# Sheet3.net
KiCad netlist of a schematic drawn in Altium Designer
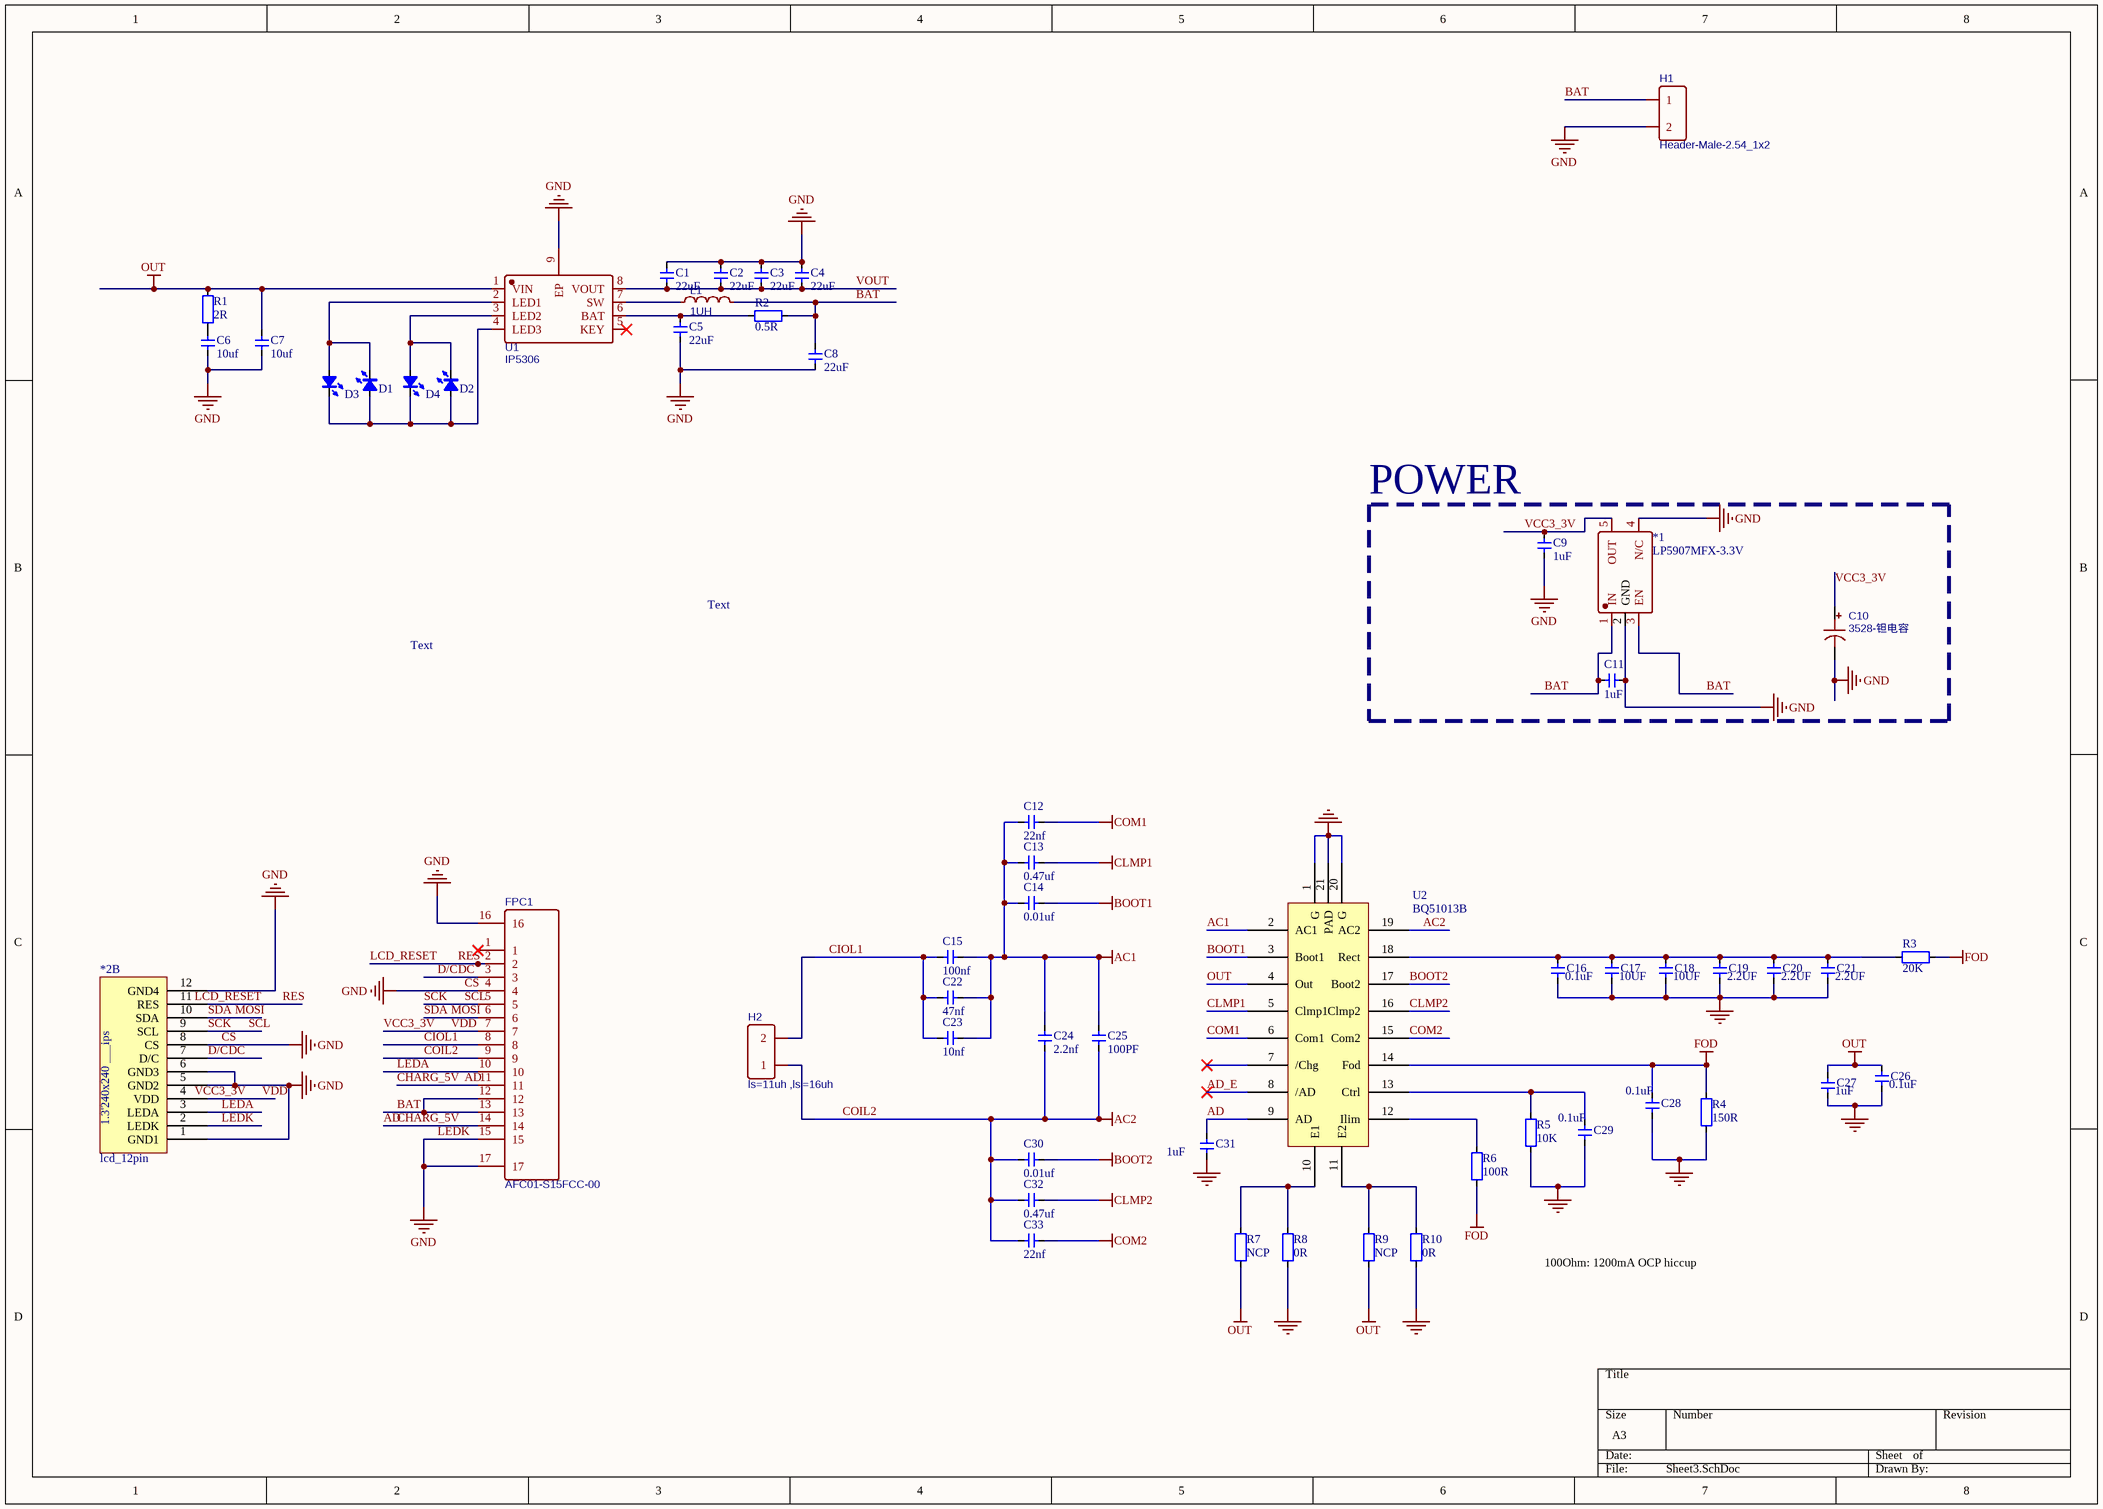
[diagram p0: Sheet3.SchDoc]

(export (version "E")
  (design (tool "Eeschema 10.0.6"))
  (components
    (comp (ref "*1")
      (value "LP5907MFX-3.3V")
      (footprint "LP5907MFX-3.3V")
      (libsource (lib "MCU") (part "LP5907MFX-3.3V"))
    )
    (comp (ref "*2")
      (value "lcd_12pin")
      (footprint "1.3‘240x240__ips")
      (libsource (lib "接插件") (part "lcd_12pin"))
    )
    (comp (ref "C1")
      (value "22uF")
      (footprint "CAP_0402")
      (description "Capacitor")
      (libsource (lib "BASE") (part "电容-0402"))
    )
    (comp (ref "C2")
      (value "22uF")
      (footprint "CAP_0402")
      (description "Capacitor")
      (libsource (lib "BASE") (part "电容-0402"))
    )
    (comp (ref "C3")
      (value "22uF")
      (footprint "CAP_0402")
      (description "Capacitor")
      (libsource (lib "BASE") (part "电容-0402"))
    )
    (comp (ref "C4")
      (value "22uF")
      (footprint "CAP_0402")
      (description "Capacitor")
      (libsource (lib "BASE") (part "电容-0402"))
    )
    (comp (ref "C5")
      (value "22uF")
      (footprint "CAP_0402")
      (description "Capacitor")
      (libsource (lib "BASE") (part "电容-0402"))
    )
    (comp (ref "C6")
      (value "10uf")
      (footprint "CAP_0402")
      (description "Capacitor")
      (libsource (lib "BASE") (part "电容-0402"))
    )
    (comp (ref "C7")
      (value "10uf")
      (footprint "CAP_0402")
      (description "Capacitor")
      (libsource (lib "BASE") (part "电容-0402"))
    )
    (comp (ref "C8")
      (value "22uF")
      (footprint "CAP_0402")
      (description "Capacitor")
      (libsource (lib "BASE") (part "电容-0402"))
    )
    (comp (ref "C9")
      (value "1uF")
      (footprint "CAP_0402")
      (description "Capacitor")
      (libsource (lib "BASE") (part "电容-0402"))
    )
    (comp (ref "C10")
      (value "3528-钽电容")
      (footprint "CAP-SMD_L3.5-W2.8")
      (fields
        (field (name "BOM_SUPPLIER PART") "C435294")
        (field (name "BOM_MANUFACTURER PART") "CA45-B016M476T")
        (field (name "CONTRIBUTOR") "LCSC")
      )
      (libsource (lib "BASE") (part "3528-钽电容"))
    )
    (comp (ref "C11")
      (value "1uF")
      (footprint "CAP_0402")
      (description "Capacitor")
      (libsource (lib "BASE") (part "电容-0402"))
    )
    (comp (ref "C12")
      (value "22nf")
      (footprint "CAP_0402")
      (description "Capacitor")
      (libsource (lib "BASE") (part "电容-0402"))
    )
    (comp (ref "C13")
      (value "0.47uf")
      (footprint "CAP_0402")
      (description "Capacitor")
      (libsource (lib "BASE") (part "电容-0402"))
    )
    (comp (ref "C14")
      (value "0.01uf")
      (footprint "CAP_0402")
      (description "Capacitor")
      (libsource (lib "BASE") (part "电容-0402"))
    )
    (comp (ref "C15")
      (value "100nf")
      (footprint "CAP_0402")
      (description "Capacitor")
      (libsource (lib "BASE") (part "电容-0402"))
    )
    (comp (ref "C16")
      (value "0.1uF")
      (footprint "CAP_0402")
      (description "Capacitor")
      (libsource (lib "BASE") (part "电容-0402"))
    )
    (comp (ref "C17")
      (value "10UF")
      (footprint "CAP_0402")
      (description "Capacitor")
      (libsource (lib "BASE") (part "电容-0402"))
    )
    (comp (ref "C18")
      (value "10UF")
      (footprint "CAP_0402")
      (description "Capacitor")
      (libsource (lib "BASE") (part "电容-0402"))
    )
    (comp (ref "C19")
      (value "2.2UF")
      (footprint "CAP_0402")
      (description "Capacitor")
      (libsource (lib "BASE") (part "电容-0402"))
    )
    (comp (ref "C20")
      (value "2.2UF")
      (footprint "CAP_0402")
      (description "Capacitor")
      (libsource (lib "BASE") (part "电容-0402"))
    )
    (comp (ref "C21")
      (value "2.2UF")
      (footprint "CAP_0402")
      (description "Capacitor")
      (libsource (lib "BASE") (part "电容-0402"))
    )
    (comp (ref "C22")
      (value "47nf")
      (footprint "CAP_0402")
      (description "Capacitor")
      (libsource (lib "BASE") (part "电容-0402"))
    )
    (comp (ref "C23")
      (value "10nf")
      (footprint "CAP_0402")
      (description "Capacitor")
      (libsource (lib "BASE") (part "电容-0402"))
    )
    (comp (ref "C24")
      (value "2.2nf")
      (footprint "CAP_0402")
      (description "Capacitor")
      (libsource (lib "BASE") (part "电容-0402"))
    )
    (comp (ref "C25")
      (value "100PF")
      (footprint "CAP_0402")
      (description "Capacitor")
      (libsource (lib "BASE") (part "电容-0402"))
    )
    (comp (ref "C26")
      (value "0.1uF")
      (footprint "CAP_0402")
      (description "Capacitor")
      (libsource (lib "BASE") (part "电容-0402"))
    )
    (comp (ref "C27")
      (value "1uF")
      (footprint "CAP_0402")
      (description "Capacitor")
      (libsource (lib "BASE") (part "电容-0402"))
    )
    (comp (ref "C28")
      (value "0.1uF")
      (footprint "CAP_0402")
      (description "Capacitor")
      (libsource (lib "BASE") (part "电容-0402"))
    )
    (comp (ref "C29")
      (value "0.1uF")
      (footprint "CAP_0402")
      (description "Capacitor")
      (libsource (lib "BASE") (part "电容-0402"))
    )
    (comp (ref "C30")
      (value "0.01uf")
      (footprint "CAP_0402")
      (description "Capacitor")
      (libsource (lib "BASE") (part "电容-0402"))
    )
    (comp (ref "C31")
      (value "1uF")
      (footprint "CAP_0402")
      (description "Capacitor")
      (libsource (lib "BASE") (part "电容-0402"))
    )
    (comp (ref "C32")
      (value "0.47uf")
      (footprint "CAP_0402")
      (description "Capacitor")
      (libsource (lib "BASE") (part "电容-0402"))
    )
    (comp (ref "C33")
      (value "22nf")
      (footprint "CAP_0402")
      (description "Capacitor")
      (libsource (lib "BASE") (part "电容-0402"))
    )
    (comp (ref "D1")
      (value "color?")
      (footprint "LED_0402_GREEN")
      (description "LED")
      (libsource (lib "BASE") (part "LED灯_0402"))
    )
    (comp (ref "D2")
      (value "color?")
      (footprint "LED_0402_GREEN")
      (description "LED")
      (libsource (lib "BASE") (part "LED灯_0402"))
    )
    (comp (ref "D3")
      (value "color?")
      (footprint "LED_0402_GREEN")
      (description "LED")
      (libsource (lib "") (part "LED灯_0402_1"))
    )
    (comp (ref "D4")
      (value "color?")
      (footprint "LED_0402_GREEN")
      (description "LED")
      (libsource (lib "") (part "LED灯_0402_1"))
    )
    (comp (ref "FPC1")
      (value "AFC01-S15FCC-00")
      (footprint "FPC-SMD_AFC01-S15FCC-00")
      (fields (field (name "BOM_SUPPLIER PART") "C262271") (field (name "CONTRIBUTOR") "LCSC"))
      (libsource (lib "接插件") (part "FPC-15P-0.5-AFC01-S15FCC-00"))
    )
    (comp (ref "H1")
      (value "Header-Male-2.54_1x2")
      (footprint "HDR-TH_2P-P2.54-V")
      (fields (field (name "BOM_MANUFACTURER PART") "826629-2") (field (name "BOM_SUPPLIER PART") "C86471"))
      (libsource (lib "接插件") (part "排针-1*2"))
    )
    (comp (ref "H2")
      (value "ls=11uh ,ls'=16uh")
      (footprint "HDR-TH_2P-P2.54-V")
      (fields (field (name "BOM_MANUFACTURER PART") "826629-2") (field (name "BOM_SUPPLIER PART") "C86471"))
      (libsource (lib "接插件") (part "排针-1*2"))
    )
    (comp (ref "L1")
      (value "1UH")
      (footprint "IND-SMD_L4.2-W4.2_MS0420-XX")
      (description "电感-0420")
      (fields
        (field (name "BOM_SUPPLIER PART") "C380158")
        (field (name "BOM_MANUFACTURER PART") "MS0420-100M")
        (field (name "CONTRIBUTOR") "LCSC")
      )
      (libsource (lib "BASE") (part "电感-0420"))
    )
    (comp (ref "R1")
      (value "2R")
      (footprint "RES_0402")
      (description "Resistor")
      (libsource (lib "") (part "电阻-0402_1"))
    )
    (comp (ref "R2")
      (value "0.5R")
      (footprint "R0603")
      (description "Resistor")
      (libsource (lib "BASE") (part "电阻-0603"))
    )
    (comp (ref "R3")
      (value "20K")
      (footprint "RES_0402")
      (description "Resistor")
      (libsource (lib "BASE") (part "电阻-0402"))
    )
    (comp (ref "R4")
      (value "150R")
      (footprint "RES_0402")
      (description "Resistor")
      (libsource (lib "") (part "电阻-0402_1"))
    )
    (comp (ref "R5")
      (value "10K")
      (footprint "RES_0402")
      (description "Resistor")
      (libsource (lib "") (part "电阻-0402_1"))
    )
    (comp (ref "R6")
      (value "100R")
      (footprint "RES_0402")
      (description "Resistor")
      (libsource (lib "") (part "电阻-0402_1"))
    )
    (comp (ref "R7")
      (value "NCP")
      (footprint "RES_0402")
      (description "Resistor")
      (libsource (lib "") (part "电阻-0402_1"))
    )
    (comp (ref "R8")
      (value "0R")
      (footprint "RES_0402")
      (description "Resistor")
      (libsource (lib "") (part "电阻-0402_1"))
    )
    (comp (ref "R9")
      (value "NCP")
      (footprint "RES_0402")
      (description "Resistor")
      (libsource (lib "") (part "电阻-0402_1"))
    )
    (comp (ref "R10")
      (value "0R")
      (footprint "RES_0402")
      (description "Resistor")
      (libsource (lib "") (part "电阻-0402_1"))
    )
    (comp (ref "U1")
      (value "IP5306")
      (footprint "ESOP-8_L4.9-W3.9-P1.27-LS6.0-BL-EP")
      (description "充电宝芯片_支持边充边放")
      (fields (field (name "BOM_SUPPLIER PART") "C181692") (field (name "CONTRIBUTOR") "LCSC"))
      (libsource (lib "MCU") (part "IP5306"))
    )
    (comp (ref "U2")
      (value "BQ51013B")
      (footprint "IC_MSP430FR2522IRHLR")
      (description "无线充电接受，qi")
      (libsource (lib "Schlib3") (part "BQ51013B"))
    )
  )
  (nets
    (net (code "1") (name "/AD") (class "Default")
      (node (ref "C31") (pin "1") (pinfunction "1_1") (pintype "passive"))
      (node (ref "FPC1") (pin "11") (pinfunction "11_11") (pintype "passive"))
      (node (ref "FPC1") (pin "14") (pinfunction "14_14") (pintype "passive"))
      (node (ref "U2") (pin "9") (pinfunction "AD_9") (pintype "passive"))
    )
    (net (code "2") (name "/AD_E") (class "Default")
      (node (ref "U2") (pin "8") (pinfunction "/AD_8") (pintype "passive+no_connect"))
    )
    (net (code "3") (name "/BAT") (class "Default")
      (node (ref "*1") (pin "1") (pinfunction "IN_1") (pintype "passive"))
      (node (ref "*1") (pin "3") (pinfunction "EN_3") (pintype "passive"))
      (node (ref "C11") (pin "2") (pinfunction "2_2") (pintype "passive"))
      (node (ref "C8") (pin "1") (pinfunction "1_1") (pintype "passive"))
      (node (ref "FPC1") (pin "12") (pinfunction "12_12") (pintype "passive"))
      (node (ref "FPC1") (pin "13") (pinfunction "13_13") (pintype "passive"))
      (node (ref "H1") (pin "1") (pinfunction "1_1") (pintype "passive"))
      (node (ref "L1") (pin "2") (pinfunction "2_2") (pintype "passive"))
      (node (ref "R2") (pin "1") (pinfunction "1_1") (pintype "passive"))
    )
    (net (code "4") (name "/CIOL1") (class "Default")
      (node (ref "C15") (pin "1") (pinfunction "1_1") (pintype "passive"))
      (node (ref "C22") (pin "1") (pinfunction "1_1") (pintype "passive"))
      (node (ref "C23") (pin "1") (pinfunction "1_1") (pintype "passive"))
      (node (ref "FPC1") (pin "8") (pinfunction "8_8") (pintype "passive"))
      (node (ref "H2") (pin "2") (pinfunction "2_2") (pintype "passive"))
    )
    (net (code "5") (name "/DC") (class "Default")
      (node (ref "*2") (pin "7") (pinfunction "D/C_7") (pintype "passive"))
      (node (ref "FPC1") (pin "3") (pinfunction "3_3") (pintype "passive"))
    )
    (net (code "6") (name "/LCD_RESET") (class "Default")
      (node (ref "*2") (pin "11") (pinfunction "RES_11") (pintype "passive"))
      (node (ref "FPC1") (pin "2") (pinfunction "2_2") (pintype "passive"))
    )
    (net (code "7") (name "/LEDA") (class "Default")
      (node (ref "*2") (pin "3") (pinfunction "LEDA_3") (pintype "passive"))
      (node (ref "FPC1") (pin "10") (pinfunction "10_10") (pintype "passive"))
    )
    (net (code "8") (name "/MOSI") (class "Default")
      (node (ref "*2") (pin "10") (pinfunction "SDA_10") (pintype "passive"))
      (node (ref "FPC1") (pin "6") (pinfunction "6_6") (pintype "passive"))
    )
    (net (code "9") (name "/SCK") (class "Default")
      (node (ref "*2") (pin "9") (pinfunction "SCL_9") (pintype "passive"))
      (node (ref "FPC1") (pin "5") (pinfunction "5_5") (pintype "passive"))
    )
    (net (code "10") (name "/VCC3_3V") (class "Default")
      (node (ref "*1") (pin "5") (pinfunction "OUT_5") (pintype "passive"))
      (node (ref "*2") (pin "4") (pinfunction "VDD_4") (pintype "passive"))
      (node (ref "C10") (pin "1") (pinfunction "1_1") (pintype "passive"))
      (node (ref "C9") (pin "1") (pinfunction "1_1") (pintype "passive"))
      (node (ref "FPC1") (pin "7") (pinfunction "7_7") (pintype "passive"))
    )
    (net (code "11") (name "/VOUT") (class "Default")
      (node (ref "C1") (pin "2") (pinfunction "2_2") (pintype "passive"))
      (node (ref "C2") (pin "2") (pinfunction "2_2") (pintype "passive"))
      (node (ref "C3") (pin "2") (pinfunction "2_2") (pintype "passive"))
      (node (ref "C4") (pin "2") (pinfunction "2_2") (pintype "passive"))
      (node (ref "U1") (pin "8") (pinfunction "VOUT_8") (pintype "passive"))
    )
    (net (code "12") (name "AC1") (class "Default")
      (node (ref "C12") (pin "1") (pinfunction "1_1") (pintype "passive"))
      (node (ref "C13") (pin "1") (pinfunction "1_1") (pintype "passive"))
      (node (ref "C14") (pin "1") (pinfunction "1_1") (pintype "passive"))
      (node (ref "C15") (pin "2") (pinfunction "2_2") (pintype "passive"))
      (node (ref "C22") (pin "2") (pinfunction "2_2") (pintype "passive"))
      (node (ref "C23") (pin "2") (pinfunction "2_2") (pintype "passive"))
      (node (ref "C24") (pin "2") (pinfunction "2_2") (pintype "passive"))
      (node (ref "C25") (pin "2") (pinfunction "2_2") (pintype "passive"))
      (node (ref "U2") (pin "2") (pinfunction "AC1_2") (pintype "passive"))
    )
    (net (code "13") (name "AC2") (class "Default")
      (node (ref "C24") (pin "1") (pinfunction "1_1") (pintype "passive"))
      (node (ref "C25") (pin "1") (pinfunction "1_1") (pintype "passive"))
      (node (ref "C30") (pin "1") (pinfunction "1_1") (pintype "passive"))
      (node (ref "C32") (pin "1") (pinfunction "1_1") (pintype "passive"))
      (node (ref "C33") (pin "1") (pinfunction "1_1") (pintype "passive"))
      (node (ref "FPC1") (pin "9") (pinfunction "9_9") (pintype "passive"))
      (node (ref "H2") (pin "1") (pinfunction "1_1") (pintype "passive"))
      (node (ref "U2") (pin "19") (pinfunction "AC2_19") (pintype "passive"))
    )
    (net (code "14") (name "BOOT1") (class "Default")
      (node (ref "C14") (pin "2") (pinfunction "2_2") (pintype "passive"))
      (node (ref "U2") (pin "3") (pinfunction "Boot1_3") (pintype "passive"))
    )
    (net (code "15") (name "BOOT2") (class "Default")
      (node (ref "C30") (pin "2") (pinfunction "2_2") (pintype "passive"))
      (node (ref "U2") (pin "17") (pinfunction "Boot2_17") (pintype "passive"))
    )
    (net (code "16") (name "CLMP1") (class "Default")
      (node (ref "C13") (pin "2") (pinfunction "2_2") (pintype "passive"))
      (node (ref "U2") (pin "5") (pinfunction "Clmp1_5") (pintype "passive"))
    )
    (net (code "17") (name "CLMP2") (class "Default")
      (node (ref "C32") (pin "2") (pinfunction "2_2") (pintype "passive"))
      (node (ref "U2") (pin "16") (pinfunction "Clmp2_16") (pintype "passive"))
    )
    (net (code "18") (name "COM1") (class "Default")
      (node (ref "C12") (pin "2") (pinfunction "2_2") (pintype "passive"))
      (node (ref "U2") (pin "6") (pinfunction "Com1_6") (pintype "passive"))
    )
    (net (code "19") (name "COM2") (class "Default")
      (node (ref "C33") (pin "2") (pinfunction "2_2") (pintype "passive"))
      (node (ref "U2") (pin "15") (pinfunction "Com2_15") (pintype "passive"))
    )
    (net (code "20") (name "FOD") (class "Default")
      (node (ref "C28") (pin "1") (pinfunction "1_1") (pintype "passive"))
      (node (ref "R3") (pin "2") (pinfunction "2_2") (pintype "passive"))
      (node (ref "R4") (pin "1") (pinfunction "1_1") (pintype "passive"))
      (node (ref "R6") (pin "2") (pinfunction "2_2") (pintype "passive"))
      (node (ref "U2") (pin "14") (pinfunction "Fod_14") (pintype "passive"))
    )
    (net (code "21") (name "GND") (class "Default")
      (node (ref "*1") (pin "2") (pinfunction "GND_2") (pintype "passive"))
      (node (ref "*1") (pin "4") (pinfunction "N/C_4") (pintype "passive"))
      (node (ref "*2") (pin "1") (pinfunction "GND1_1") (pintype "passive"))
      (node (ref "*2") (pin "12") (pinfunction "GND4_12") (pintype "passive"))
      (node (ref "*2") (pin "2") (pinfunction "LEDK_2") (pintype "passive"))
      (node (ref "*2") (pin "5") (pinfunction "GND2_5") (pintype "passive"))
      (node (ref "*2") (pin "6") (pinfunction "GND3_6") (pintype "passive"))
      (node (ref "*2") (pin "8") (pinfunction "CS_8") (pintype "passive"))
      (node (ref "C1") (pin "1") (pinfunction "1_1") (pintype "passive"))
      (node (ref "C10") (pin "2") (pinfunction "2_2") (pintype "passive"))
      (node (ref "C11") (pin "1") (pinfunction "1_1") (pintype "passive"))
      (node (ref "C16") (pin "2") (pinfunction "2_2") (pintype "passive"))
      (node (ref "C17") (pin "2") (pinfunction "2_2") (pintype "passive"))
      (node (ref "C18") (pin "2") (pinfunction "2_2") (pintype "passive"))
      (node (ref "C19") (pin "2") (pinfunction "2_2") (pintype "passive"))
      (node (ref "C2") (pin "1") (pinfunction "1_1") (pintype "passive"))
      (node (ref "C20") (pin "2") (pinfunction "2_2") (pintype "passive"))
      (node (ref "C21") (pin "2") (pinfunction "2_2") (pintype "passive"))
      (node (ref "C26") (pin "2") (pinfunction "2_2") (pintype "passive"))
      (node (ref "C27") (pin "2") (pinfunction "2_2") (pintype "passive"))
      (node (ref "C28") (pin "2") (pinfunction "2_2") (pintype "passive"))
      (node (ref "C29") (pin "2") (pinfunction "2_2") (pintype "passive"))
      (node (ref "C3") (pin "1") (pinfunction "1_1") (pintype "passive"))
      (node (ref "C31") (pin "2") (pinfunction "2_2") (pintype "passive"))
      (node (ref "C4") (pin "1") (pinfunction "1_1") (pintype "passive"))
      (node (ref "C5") (pin "2") (pinfunction "2_2") (pintype "passive"))
      (node (ref "C6") (pin "1") (pinfunction "1_1") (pintype "passive"))
      (node (ref "C7") (pin "1") (pinfunction "1_1") (pintype "passive"))
      (node (ref "C8") (pin "2") (pinfunction "2_2") (pintype "passive"))
      (node (ref "C9") (pin "2") (pinfunction "2_2") (pintype "passive"))
      (node (ref "FPC1") (pin "15") (pinfunction "15_15") (pintype "passive"))
      (node (ref "FPC1") (pin "16") (pinfunction "16_16") (pintype "passive"))
      (node (ref "FPC1") (pin "17") (pinfunction "17_17") (pintype "passive"))
      (node (ref "FPC1") (pin "4") (pinfunction "4_4") (pintype "passive"))
      (node (ref "H1") (pin "2") (pinfunction "2_2") (pintype "passive"))
      (node (ref "R10") (pin "2") (pinfunction "2_2") (pintype "passive"))
      (node (ref "R4") (pin "2") (pinfunction "2_2") (pintype "passive"))
      (node (ref "R5") (pin "2") (pinfunction "2_2") (pintype "passive"))
      (node (ref "R8") (pin "2") (pinfunction "2_2") (pintype "passive"))
      (node (ref "U1") (pin "9") (pinfunction "EP_9") (pintype "passive"))
      (node (ref "U2") (pin "1") (pinfunction "G_1") (pintype "passive"))
      (node (ref "U2") (pin "20") (pinfunction "G_20") (pintype "passive"))
      (node (ref "U2") (pin "21") (pinfunction "PAD_21") (pintype "passive"))
    )
    (net (code "22") (name "Net-(C6-Pad2)") (class "Default")
      (node (ref "C6") (pin "2") (pinfunction "2_2") (pintype "passive"))
      (node (ref "R1") (pin "2") (pinfunction "2_2") (pintype "passive"))
    )
    (net (code "23") (name "Net-(D1-A)") (class "Default")
      (node (ref "D1") (pin "1") (pinfunction "A_1") (pintype "passive"))
      (node (ref "D2") (pin "1") (pinfunction "A_1") (pintype "passive"))
      (node (ref "D3") (pin "2") (pinfunction "K_2") (pintype "passive"))
      (node (ref "D4") (pin "2") (pinfunction "K_2") (pintype "passive"))
      (node (ref "U1") (pin "4") (pinfunction "LED3_4") (pintype "passive"))
    )
    (net (code "24") (name "Net-(D1-K)") (class "Default")
      (node (ref "D1") (pin "2") (pinfunction "K_2") (pintype "passive"))
      (node (ref "D3") (pin "1") (pinfunction "A_1") (pintype "passive"))
      (node (ref "U1") (pin "2") (pinfunction "LED1_2") (pintype "passive"))
    )
    (net (code "25") (name "Net-(D2-K)") (class "Default")
      (node (ref "D2") (pin "2") (pinfunction "K_2") (pintype "passive"))
      (node (ref "D4") (pin "1") (pinfunction "A_1") (pintype "passive"))
      (node (ref "U1") (pin "3") (pinfunction "LED2_3") (pintype "passive"))
    )
    (net (code "26") (name "Net-(U1-BAT)") (class "Default")
      (node (ref "C5") (pin "1") (pinfunction "1_1") (pintype "passive"))
      (node (ref "R2") (pin "2") (pinfunction "2_2") (pintype "passive"))
      (node (ref "U1") (pin "6") (pinfunction "BAT_6") (pintype "passive"))
    )
    (net (code "27") (name "Net-(U1-SW)") (class "Default")
      (node (ref "L1") (pin "1") (pinfunction "1_1") (pintype "passive"))
      (node (ref "U1") (pin "7") (pinfunction "SW_7") (pintype "passive"))
    )
    (net (code "28") (name "Net-(U2-Ctrl)") (class "Default")
      (node (ref "C29") (pin "1") (pinfunction "1_1") (pintype "passive"))
      (node (ref "R5") (pin "1") (pinfunction "1_1") (pintype "passive"))
      (node (ref "U2") (pin "13") (pinfunction "Ctrl_13") (pintype "passive"))
    )
    (net (code "29") (name "Net-(U2-E1)") (class "Default")
      (node (ref "R7") (pin "1") (pinfunction "1_1") (pintype "passive"))
      (node (ref "R8") (pin "1") (pinfunction "1_1") (pintype "passive"))
      (node (ref "U2") (pin "10") (pinfunction "E1_10") (pintype "passive"))
    )
    (net (code "30") (name "Net-(U2-E2)") (class "Default")
      (node (ref "R10") (pin "1") (pinfunction "1_1") (pintype "passive"))
      (node (ref "R9") (pin "1") (pinfunction "1_1") (pintype "passive"))
      (node (ref "U2") (pin "11") (pinfunction "E2_11") (pintype "passive"))
    )
    (net (code "31") (name "Net-(U2-Ilim)") (class "Default")
      (node (ref "R6") (pin "1") (pinfunction "1_1") (pintype "passive"))
      (node (ref "U2") (pin "12") (pinfunction "Ilim_12") (pintype "passive"))
    )
    (net (code "32") (name "Net-(U2-Rect)") (class "Default")
      (node (ref "C16") (pin "1") (pinfunction "1_1") (pintype "passive"))
      (node (ref "C17") (pin "1") (pinfunction "1_1") (pintype "passive"))
      (node (ref "C18") (pin "1") (pinfunction "1_1") (pintype "passive"))
      (node (ref "C19") (pin "1") (pinfunction "1_1") (pintype "passive"))
      (node (ref "C20") (pin "1") (pinfunction "1_1") (pintype "passive"))
      (node (ref "C21") (pin "1") (pinfunction "1_1") (pintype "passive"))
      (node (ref "R3") (pin "1") (pinfunction "1_1") (pintype "passive"))
      (node (ref "U2") (pin "18") (pinfunction "Rect_18") (pintype "passive"))
    )
    (net (code "33") (name "OUT") (class "Default")
      (node (ref "C26") (pin "1") (pinfunction "1_1") (pintype "passive"))
      (node (ref "C27") (pin "1") (pinfunction "1_1") (pintype "passive"))
      (node (ref "C7") (pin "2") (pinfunction "2_2") (pintype "passive"))
      (node (ref "R1") (pin "1") (pinfunction "1_1") (pintype "passive"))
      (node (ref "R7") (pin "2") (pinfunction "2_2") (pintype "passive"))
      (node (ref "R9") (pin "2") (pinfunction "2_2") (pintype "passive"))
      (node (ref "U1") (pin "1") (pinfunction "VIN_1") (pintype "passive"))
      (node (ref "U2") (pin "4") (pinfunction "Out_4") (pintype "passive"))
    )
    (net (code "34") (name "unconnected-(FPC1-Pad1)") (class "Default")
      (node (ref "FPC1") (pin "1") (pinfunction "1_1") (pintype "passive+no_connect"))
    )
    (net (code "35") (name "unconnected-(U1-KEY-Pad5)") (class "Default")
      (node (ref "U1") (pin "5") (pinfunction "KEY_5") (pintype "passive+no_connect"))
    )
    (net (code "36") (name "unconnected-(U2-{slash}Chg-Pad7)") (class "Default")
      (node (ref "U2") (pin "7") (pinfunction "/Chg_7") (pintype "passive+no_connect"))
    )
  )
)
